# Driver_velocidad_DCmotor.net
KiCad netlist of a schematic drawn in EAGLE
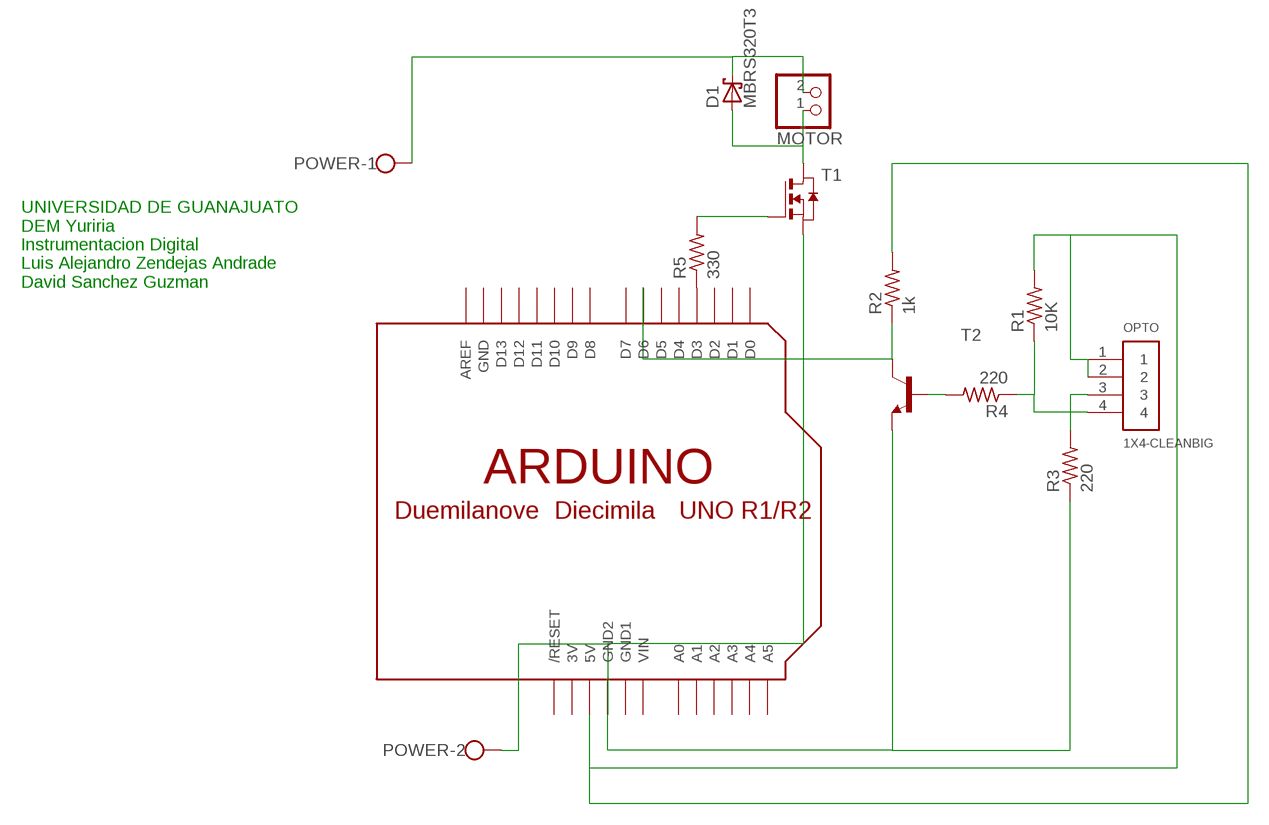
[diagram p0: schematic, sheet 1]

(export (version "E")
  (design (tool "Eeschema 10.0.6"))
  (components
    (comp (ref "D1")
      (value "MBRS320T3")
      (footprint "eagle-import:SMC")
      (libsource (lib "eagle-import") (part "MBRS30T32"))
    )
    (comp (ref "MOTOR")
      (value "PINHD-1X2")
      (footprint "eagle-import:1X02")
      (libsource (lib "eagle-import") (part "PINHD-1X2"))
    )
    (comp (ref "OPTO")
      (value "1X4-CLEANBIG")
      (footprint "eagle-import:1X04-CLEANBIG")
      (libsource (lib "eagle-import") (part "1X4-CLEANBIG"))
    )
    (comp (ref "POWER")
      (value "W237-102")
      (footprint "eagle-import:W237-102")
      (fields (field (name "MPN") "237-102"))
      (libsource (lib "eagle-import") (part "W237-102"))
    )
    (comp (ref "R1")
      (value "10K")
      (footprint "eagle-import:M1206")
      (libsource (lib "eagle-import") (part "R-US_M1206"))
    )
    (comp (ref "R2")
      (value "1k")
      (footprint "eagle-import:M1206")
      (libsource (lib "eagle-import") (part "R-US_M1206"))
    )
    (comp (ref "R3")
      (value "220")
      (footprint "eagle-import:M1206")
      (libsource (lib "eagle-import") (part "R-US_M1206"))
    )
    (comp (ref "R4")
      (value "220")
      (footprint "eagle-import:M1206")
      (libsource (lib "eagle-import") (part "R-US_M1206"))
    )
    (comp (ref "R5")
      (value "330")
      (footprint "eagle-import:M1206")
      (libsource (lib "eagle-import") (part "R-US_M1206"))
    )
    (comp (ref "T1")
      (value "NMOSSOT223")
      (footprint "eagle-import:SOT223")
      (libsource (lib "eagle-import") (part "NMOSSOT223"))
    )
    (comp (ref "T2")
      (value "BC817-16-NPN-SOT23-BEC")
      (footprint "eagle-import:SOT23-BEC")
      (libsource (lib "eagle-import") (part "-NPN-SOT23-BECBC817-16"))
    )
    (comp (ref "U$1")
      (value "ARDUINO-NOHOLE")
      (footprint "eagle-import:ARDUINO-NOHOLE")
      (libsource (lib "eagle-import") (part "ARDUINO-NOHOLE"))
    )
  )
  (nets
    (net (code "1") (name "/3V") (class "Default")
      (node (ref "U$1") (pin "3V") (pinfunction "3V_3V") (pintype "power_in"))
    )
    (net (code "2") (name "/GND") (class "Default")
      (node (ref "U$1") (pin "GND") (pinfunction "GND_GND") (pintype "power_in"))
    )
    (net (code "3") (name "/GND1") (class "Default")
      (node (ref "U$1") (pin "GND1") (pinfunction "GND1_GND1") (pintype "power_in"))
    )
    (net (code "4") (name "/VIN") (class "Default")
      (node (ref "U$1") (pin "VIN") (pinfunction "VIN_VIN") (pintype "power_in"))
    )
    (net (code "5") (name "Net-(D1-PadA)") (class "Default")
      (node (ref "D1") (pin "A") (pinfunction "A_A") (pintype "passive"))
      (node (ref "MOTOR") (pin "1") (pinfunction "1_1") (pintype "passive"))
      (node (ref "T1") (pin "2") (pinfunction "D_2") (pintype "passive"))
      (node (ref "T1") (pin "4") (pinfunction "D_4") (pintype "passive"))
    )
    (net (code "6") (name "Net-(OPTO-Pad1)") (class "Default")
      (node (ref "OPTO") (pin "1") (pinfunction "1_1") (pintype "bidirectional"))
      (node (ref "OPTO") (pin "2") (pinfunction "2_2") (pintype "bidirectional"))
      (node (ref "R1") (pin "2") (pinfunction "2_2") (pintype "passive"))
      (node (ref "R2") (pin "2") (pinfunction "2_2") (pintype "passive"))
      (node (ref "U$1") (pin "5V") (pinfunction "5V_5V") (pintype "power_in"))
    )
    (net (code "7") (name "Net-(OPTO-Pad3)") (class "Default")
      (node (ref "OPTO") (pin "3") (pinfunction "3_3") (pintype "bidirectional"))
      (node (ref "R3") (pin "2") (pinfunction "2_2") (pintype "passive"))
    )
    (net (code "8") (name "Net-(OPTO-Pad4)") (class "Default")
      (node (ref "OPTO") (pin "4") (pinfunction "4_4") (pintype "bidirectional"))
      (node (ref "R1") (pin "1") (pinfunction "1_1") (pintype "passive"))
      (node (ref "R4") (pin "1") (pinfunction "1_1") (pintype "passive"))
    )
    (net (code "9") (name "Net-(POWERA-KL)") (class "Default")
      (node (ref "D1") (pin "C") (pinfunction "C_C") (pintype "passive"))
      (node (ref "MOTOR") (pin "2") (pinfunction "2_2") (pintype "passive"))
      (node (ref "POWER") (pin "1") (pinfunction "KL_1") (pintype "passive"))
    )
    (net (code "10") (name "Net-(POWERB-KL)") (class "Default")
      (node (ref "POWER") (pin "2") (pinfunction "KL_2") (pintype "passive"))
      (node (ref "R3") (pin "1") (pinfunction "1_1") (pintype "passive"))
      (node (ref "T1") (pin "3") (pinfunction "S_3") (pintype "passive"))
      (node (ref "T2") (pin "E") (pinfunction "E_E") (pintype "passive"))
      (node (ref "U$1") (pin "GND2") (pinfunction "GND2_GND2") (pintype "power_in"))
    )
    (net (code "11") (name "Net-(R2-Pad1)") (class "Default")
      (node (ref "R2") (pin "1") (pinfunction "1_1") (pintype "passive"))
      (node (ref "T2") (pin "C") (pinfunction "C_C") (pintype "passive"))
      (node (ref "U$1") (pin "D6") (pinfunction "D6_D6") (pintype "bidirectional"))
    )
    (net (code "12") (name "Net-(R4-Pad2)") (class "Default")
      (node (ref "R4") (pin "2") (pinfunction "2_2") (pintype "passive"))
      (node (ref "T2") (pin "B") (pinfunction "B_B") (pintype "passive"))
    )
    (net (code "13") (name "Net-(R5-Pad1)") (class "Default")
      (node (ref "R5") (pin "1") (pinfunction "1_1") (pintype "passive"))
      (node (ref "U$1") (pin "D3") (pinfunction "D3_D3") (pintype "bidirectional"))
    )
    (net (code "14") (name "Net-(T1-G)") (class "Default")
      (node (ref "R5") (pin "2") (pinfunction "2_2") (pintype "passive"))
      (node (ref "T1") (pin "1") (pinfunction "G_1") (pintype "passive"))
    )
    (net (code "15") (name "unconnected-(U$1-PadA0)") (class "Default")
      (node (ref "U$1") (pin "A0") (pinfunction "A0_A0") (pintype "bidirectional"))
    )
    (net (code "16") (name "unconnected-(U$1-PadA1)") (class "Default")
      (node (ref "U$1") (pin "A1") (pinfunction "A1_A1") (pintype "bidirectional"))
    )
    (net (code "17") (name "unconnected-(U$1-PadA2)") (class "Default")
      (node (ref "U$1") (pin "A2") (pinfunction "A2_A2") (pintype "bidirectional"))
    )
    (net (code "18") (name "unconnected-(U$1-PadA3)") (class "Default")
      (node (ref "U$1") (pin "A3") (pinfunction "A3_A3") (pintype "bidirectional"))
    )
    (net (code "19") (name "unconnected-(U$1-PadA4)") (class "Default")
      (node (ref "U$1") (pin "A4") (pinfunction "A4_A4") (pintype "bidirectional"))
    )
    (net (code "20") (name "unconnected-(U$1-PadA5)") (class "Default")
      (node (ref "U$1") (pin "A5") (pinfunction "A5_A5") (pintype "bidirectional"))
    )
    (net (code "21") (name "unconnected-(U$1-PadAREF)") (class "Default")
      (node (ref "U$1") (pin "AREF") (pinfunction "AREF_AREF") (pintype "bidirectional"))
    )
    (net (code "22") (name "unconnected-(U$1-PadD0)") (class "Default")
      (node (ref "U$1") (pin "D0") (pinfunction "D0_D0") (pintype "bidirectional"))
    )
    (net (code "23") (name "unconnected-(U$1-PadD1)") (class "Default")
      (node (ref "U$1") (pin "D1") (pinfunction "D1_D1") (pintype "bidirectional"))
    )
    (net (code "24") (name "unconnected-(U$1-PadD2)") (class "Default")
      (node (ref "U$1") (pin "D2") (pinfunction "D2_D2") (pintype "bidirectional"))
    )
    (net (code "25") (name "unconnected-(U$1-PadD4)") (class "Default")
      (node (ref "U$1") (pin "D4") (pinfunction "D4_D4") (pintype "bidirectional"))
    )
    (net (code "26") (name "unconnected-(U$1-PadD5)") (class "Default")
      (node (ref "U$1") (pin "D5") (pinfunction "D5_D5") (pintype "bidirectional"))
    )
    (net (code "27") (name "unconnected-(U$1-PadD7)") (class "Default")
      (node (ref "U$1") (pin "D7") (pinfunction "D7_D7") (pintype "bidirectional"))
    )
    (net (code "28") (name "unconnected-(U$1-PadD8)") (class "Default")
      (node (ref "U$1") (pin "D8") (pinfunction "D8_D8") (pintype "bidirectional"))
    )
    (net (code "29") (name "unconnected-(U$1-PadD9)") (class "Default")
      (node (ref "U$1") (pin "D9") (pinfunction "D9_D9") (pintype "bidirectional"))
    )
    (net (code "30") (name "unconnected-(U$1-PadD10)") (class "Default")
      (node (ref "U$1") (pin "D10") (pinfunction "D10_D10") (pintype "bidirectional"))
    )
    (net (code "31") (name "unconnected-(U$1-PadD11)") (class "Default")
      (node (ref "U$1") (pin "D11") (pinfunction "D11_D11") (pintype "bidirectional"))
    )
    (net (code "32") (name "unconnected-(U$1-PadD12)") (class "Default")
      (node (ref "U$1") (pin "D12") (pinfunction "D12_D12") (pintype "bidirectional"))
    )
    (net (code "33") (name "unconnected-(U$1-PadD13)") (class "Default")
      (node (ref "U$1") (pin "D13") (pinfunction "D13_D13") (pintype "bidirectional"))
    )
    (net (code "34") (name "unconnected-(U$1-{slash}RESET-PadRESET)") (class "Default")
      (node (ref "U$1") (pin "RESET") (pinfunction "/RESET_RESET") (pintype "bidirectional"))
    )
  )
)
